# Key-RTC.net
KiCad netlist of a schematic drawn in Altium Designer
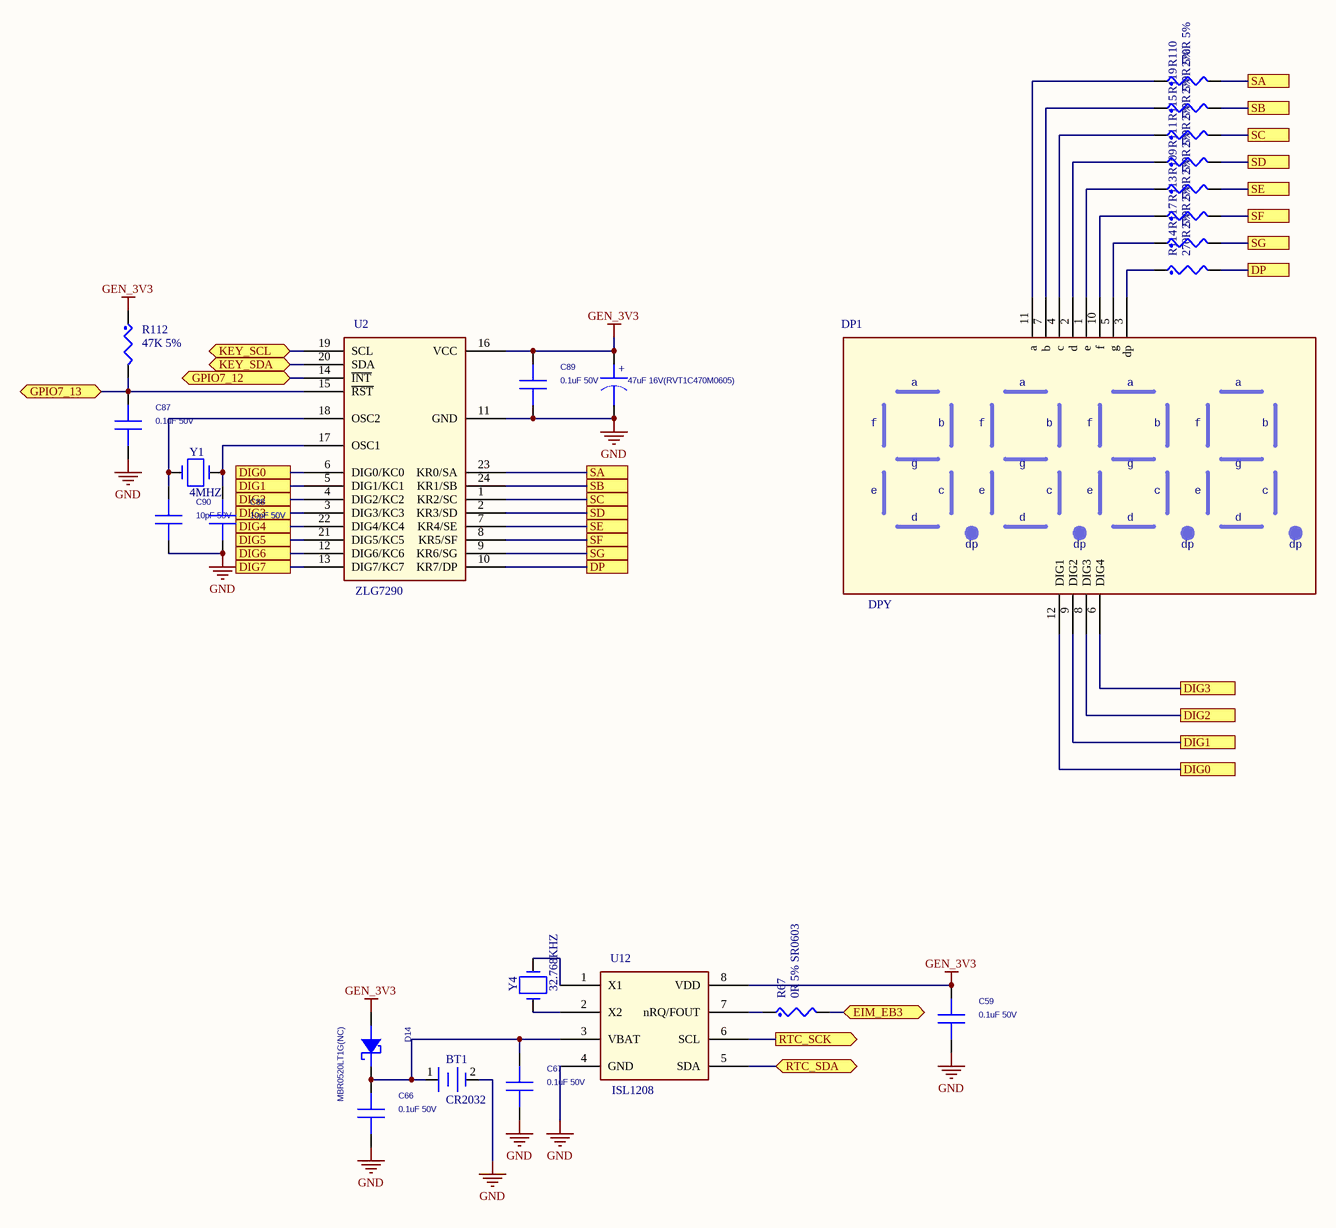
[diagram p0: Key-RTC.SchDoc]

(export (version "E")
  (design (tool "Eeschema 10.0.6"))
  (components
    (comp (ref "BT1")
      (value "CR2032")
      (footprint "CR2032")
      (libsource (lib "MY-I.MX6-SCH_Library") (part "BATTERY"))
    )
    (comp (ref "C11")
      (value "47uF 16V(RVT1C470M0605)")
      (footprint "SCA6P3X5P4")
      (description "SCA6p3x5p4")
      (fields (field (name "TOLERANCE") "20%"))
      (libsource (lib "MY-I.MX6-SCH_Library") (part "100uF-6.3V-20%-AL-LOESR-SMD_5x5"))
    )
    (comp (ref "C59")
      (value "0.1uF 50V")
      (footprint "SC0603")
      (description "Capacitor, 0.1uF, 50V, 10%, X5R, 0603")
      (fields (field (name "VOLTAGE") "6.3V") (field (name "TOLERANCE") "10%"))
      (libsource (lib "MY-I.MX6-SCH_Library") (part "0.1uF-6.3V-10%-X5R-0402"))
    )
    (comp (ref "C66")
      (value "0.1uF 50V")
      (footprint "SC0603")
      (description "Capacitor, 0.1uF, 50V, 10%, X5R, 0603")
      (fields (field (name "VOLTAGE") "6.3V") (field (name "TOLERANCE") "10%"))
      (libsource (lib "MY-I.MX6-SCH_Library") (part "0.1uF-6.3V-10%-X5R-0402"))
    )
    (comp (ref "C67")
      (value "0.1uF 50V")
      (footprint "SC0603")
      (description "Capacitor, 0.1uF, 50V, 10%, X5R, 0603")
      (fields (field (name "VOLTAGE") "6.3V") (field (name "TOLERANCE") "10%"))
      (libsource (lib "MY-I.MX6-SCH_Library") (part "0.1uF-6.3V-10%-X5R-0402"))
    )
    (comp (ref "C87")
      (value "0.1uF 50V")
      (footprint "SC0603")
      (description "Capacitor, 0.1uF, 50V, 10%, X5R, 0603")
      (fields (field (name "VOLTAGE") "6.3V") (field (name "TOLERANCE") "10%"))
      (libsource (lib "MY-I.MX6-SCH_Library") (part "0.1uF-6.3V-10%-X5R-0402"))
    )
    (comp (ref "C88")
      (value "10pF 50V")
      (footprint "SC0603")
      (description "Capacitor, 0.1uF, 50V, 10%, X5R, 0603")
      (fields (field (name "VOLTAGE") "6.3V") (field (name "TOLERANCE") "10%"))
      (libsource (lib "MY-I.MX6-SCH_Library") (part "0.1uF-6.3V-10%-X5R-0402"))
    )
    (comp (ref "C89")
      (value "0.1uF 50V")
      (footprint "SC0603")
      (description "Capacitor, 0.1uF, 50V, 10%, X5R, 0603")
      (fields (field (name "VOLTAGE") "6.3V") (field (name "TOLERANCE") "10%"))
      (libsource (lib "MY-I.MX6-SCH_Library") (part "0.1uF-6.3V-10%-X5R-0402"))
    )
    (comp (ref "C90")
      (value "10pF 50V")
      (footprint "SC0603")
      (description "Capacitor, 0.1uF, 50V, 10%, X5R, 0603")
      (fields (field (name "VOLTAGE") "6.3V") (field (name "TOLERANCE") "10%"))
      (libsource (lib "MY-I.MX6-SCH_Library") (part "0.1uF-6.3V-10%-X5R-0402"))
    )
    (comp (ref "D14")
      (value "MBR0520LT1G(NC)")
      (footprint "SOD123")
      (description "SOD123")
      (libsource (lib "MY-I.MX6-SCH_Library") (part "DIODE SCHOTTKY_Dup1"))
    )
    (comp (ref "DP1")
      (value "DPY")
      (footprint "LEDTUBE-14X30")
      (libsource (lib "MY-I.MX6-SCH_Library") (part "DPY"))
    )
    (comp (ref "R67")
      (value "0R 5% SR0603")
      (footprint "SR0603")
      (libsource (lib "MY-I.MX6-SCH_Library") (part "RES"))
    )
    (comp (ref "R109")
      (value "270R 5%")
      (footprint "SR0603")
      (description "SR0603")
      (libsource (lib "MY-I.MX6-SCH_Library") (part "RES"))
    )
    (comp (ref "R110")
      (value "270R 5%")
      (footprint "SR0603")
      (description "SR0603")
      (libsource (lib "MY-I.MX6-SCH_Library") (part "RES"))
    )
    (comp (ref "R111")
      (value "270R 5%")
      (footprint "SR0603")
      (description "SR0603")
      (libsource (lib "MY-I.MX6-SCH_Library") (part "RES"))
    )
    (comp (ref "R112")
      (value "47K 5%")
      (footprint "SR0603")
      (description "SR0603")
      (libsource (lib "MY-I.MX6-SCH_Library") (part "RES"))
    )
    (comp (ref "R113")
      (value "270R 5%")
      (footprint "SR0603")
      (description "SR0603")
      (libsource (lib "MY-I.MX6-SCH_Library") (part "RES"))
    )
    (comp (ref "R114")
      (value "270R 5%")
      (footprint "SR0603")
      (description "SR0603")
      (libsource (lib "MY-I.MX6-SCH_Library") (part "RES"))
    )
    (comp (ref "R115")
      (value "270R 5%")
      (footprint "SR0603")
      (description "SR0603")
      (libsource (lib "MY-I.MX6-SCH_Library") (part "RES"))
    )
    (comp (ref "R117")
      (value "270R 5%")
      (footprint "SR0603")
      (description "SR0603")
      (libsource (lib "MY-I.MX6-SCH_Library") (part "RES"))
    )
    (comp (ref "R119")
      (value "270R 5%")
      (footprint "SR0603")
      (description "SR0603")
      (libsource (lib "MY-I.MX6-SCH_Library") (part "RES"))
    )
    (comp (ref "U2")
      (value "ZLG7290")
      (footprint "SOP24-1P27-15X10P5")
      (description "SOP24-1p27-15x10p5")
      (libsource (lib "MY-I.MX6-SCH_Library") (part "ZLG7290"))
    )
    (comp (ref "U12")
      (value "ISL1208")
      (footprint "SOP8-1p27-5x4")
      (description "SL1208  SOP8-1p27-5x4")
      (libsource (lib "MY-I.MX6-SCH_Library") (part "ISL1208"))
    )
    (comp (ref "Y1")
      (value "4MHZ")
      (footprint "XTAL-2-5P08")
      (description "XTAL-2-5p08")
      (libsource (lib "MY-I.MX6-SCH_Library") (part "CRYSTAL_0"))
    )
    (comp (ref "Y4")
      (value "32.768KHZ")
      (footprint "SCRY2-3X1P5")
      (description "SCRY2-3x1p5")
      (libsource (lib "MY-I.MX6-SCH_Library") (part "CRYSTAL_0"))
    )
  )
  (nets
    (net (code "1") (name "/DIG0") (class "Default")
      (node (ref "DP1") (pin "12") (pinfunction "DIG1_12") (pintype "passive"))
      (node (ref "U2") (pin "6") (pinfunction "DIG0/KC0_6") (pintype "passive"))
    )
    (net (code "2") (name "/DIG1") (class "Default")
      (node (ref "DP1") (pin "9") (pinfunction "DIG2_9") (pintype "passive"))
      (node (ref "U2") (pin "5") (pinfunction "DIG1/KC1_5") (pintype "passive"))
    )
    (net (code "3") (name "/DIG2") (class "Default")
      (node (ref "DP1") (pin "8") (pinfunction "DIG3_8") (pintype "passive"))
      (node (ref "U2") (pin "4") (pinfunction "DIG2/KC2_4") (pintype "passive"))
    )
    (net (code "4") (name "/DIG3") (class "Default")
      (node (ref "DP1") (pin "6") (pinfunction "DIG4_6") (pintype "passive"))
      (node (ref "U2") (pin "3") (pinfunction "DIG3/KC3_3") (pintype "passive"))
    )
    (net (code "5") (name "/DIG4") (class "Default")
      (node (ref "U2") (pin "22") (pinfunction "DIG4/KC4_22") (pintype "passive"))
    )
    (net (code "6") (name "/DIG5") (class "Default")
      (node (ref "U2") (pin "21") (pinfunction "DIG5/KC5_21") (pintype "passive"))
    )
    (net (code "7") (name "/DIG6") (class "Default")
      (node (ref "U2") (pin "12") (pinfunction "DIG6/KC6_12") (pintype "passive"))
    )
    (net (code "8") (name "/DIG7") (class "Default")
      (node (ref "U2") (pin "13") (pinfunction "DIG7/KC7_13") (pintype "passive"))
    )
    (net (code "9") (name "/DP") (class "Default")
      (node (ref "R114") (pin "2") (pinfunction "2_2") (pintype "passive"))
      (node (ref "U2") (pin "10") (pinfunction "KR7/DP_10") (pintype "passive"))
    )
    (net (code "10") (name "/EIM_EB3") (class "Default")
      (node (ref "R67") (pin "2") (pinfunction "2_2") (pintype "passive"))
    )
    (net (code "11") (name "/GPIO7_12") (class "Default")
      (node (ref "U2") (pin "14") (pinfunction "~{INT}_14") (pintype "passive"))
    )
    (net (code "12") (name "/GPIO7_13") (class "Default")
      (node (ref "C87") (pin "1") (pinfunction "1_1") (pintype "passive"))
      (node (ref "R112") (pin "2") (pinfunction "2_2") (pintype "passive"))
      (node (ref "U2") (pin "15") (pinfunction "~{RST}_15") (pintype "passive"))
    )
    (net (code "13") (name "/KEY_SCL") (class "Default")
      (node (ref "U2") (pin "19") (pinfunction "SCL_19") (pintype "passive"))
    )
    (net (code "14") (name "/KEY_SDA") (class "Default")
      (node (ref "U2") (pin "20") (pinfunction "SDA_20") (pintype "passive"))
    )
    (net (code "15") (name "/RTC_SCK") (class "Default")
      (node (ref "U12") (pin "6") (pinfunction "SCL_6") (pintype "passive"))
    )
    (net (code "16") (name "/RTC_SDA") (class "Default")
      (node (ref "U12") (pin "5") (pinfunction "SDA_5") (pintype "passive"))
    )
    (net (code "17") (name "/SA") (class "Default")
      (node (ref "R110") (pin "2") (pinfunction "2_2") (pintype "passive"))
      (node (ref "U2") (pin "23") (pinfunction "KR0/SA_23") (pintype "passive"))
    )
    (net (code "18") (name "/SB") (class "Default")
      (node (ref "R119") (pin "2") (pinfunction "2_2") (pintype "passive"))
      (node (ref "U2") (pin "24") (pinfunction "KR1/SB_24") (pintype "passive"))
    )
    (net (code "19") (name "/SC") (class "Default")
      (node (ref "R115") (pin "2") (pinfunction "2_2") (pintype "passive"))
      (node (ref "U2") (pin "1") (pinfunction "KR2/SC_1") (pintype "passive"))
    )
    (net (code "20") (name "/SD") (class "Default")
      (node (ref "R111") (pin "2") (pinfunction "2_2") (pintype "passive"))
      (node (ref "U2") (pin "2") (pinfunction "KR3/SD_2") (pintype "passive"))
    )
    (net (code "21") (name "/SE") (class "Default")
      (node (ref "R109") (pin "2") (pinfunction "2_2") (pintype "passive"))
      (node (ref "U2") (pin "7") (pinfunction "KR4/SE_7") (pintype "passive"))
    )
    (net (code "22") (name "/SF") (class "Default")
      (node (ref "R113") (pin "2") (pinfunction "2_2") (pintype "passive"))
      (node (ref "U2") (pin "8") (pinfunction "KR5/SF_8") (pintype "passive"))
    )
    (net (code "23") (name "/SG") (class "Default")
      (node (ref "R117") (pin "2") (pinfunction "2_2") (pintype "passive"))
      (node (ref "U2") (pin "9") (pinfunction "KR6/SG_9") (pintype "passive"))
    )
    (net (code "24") (name "GEN_3V3") (class "Default")
      (node (ref "C11") (pin "1") (pinfunction "1_1") (pintype "passive"))
      (node (ref "C59") (pin "1") (pinfunction "1_1") (pintype "passive"))
      (node (ref "C89") (pin "1") (pinfunction "1_1") (pintype "passive"))
      (node (ref "D14") (pin "1") (pinfunction "ANODE_1") (pintype "passive"))
      (node (ref "R112") (pin "1") (pinfunction "1_1") (pintype "passive"))
      (node (ref "U12") (pin "8") (pinfunction "VDD_8") (pintype "passive"))
      (node (ref "U2") (pin "16") (pinfunction "VCC_16") (pintype "passive"))
    )
    (net (code "25") (name "GND") (class "Default")
      (node (ref "BT1") (pin "2") (pinfunction "2_2") (pintype "passive"))
      (node (ref "C11") (pin "2") (pinfunction "2_2") (pintype "passive"))
      (node (ref "C59") (pin "2") (pinfunction "2_2") (pintype "passive"))
      (node (ref "C66") (pin "2") (pinfunction "2_2") (pintype "passive"))
      (node (ref "C67") (pin "2") (pinfunction "2_2") (pintype "passive"))
      (node (ref "C87") (pin "2") (pinfunction "2_2") (pintype "passive"))
      (node (ref "C88") (pin "2") (pinfunction "2_2") (pintype "passive"))
      (node (ref "C89") (pin "2") (pinfunction "2_2") (pintype "passive"))
      (node (ref "C90") (pin "2") (pinfunction "2_2") (pintype "passive"))
      (node (ref "U12") (pin "4") (pinfunction "GND_4") (pintype "passive"))
      (node (ref "U2") (pin "11") (pinfunction "GND_11") (pintype "passive"))
    )
    (net (code "26") (name "Net-(D14-CATHODE)") (class "Default")
      (node (ref "BT1") (pin "1") (pinfunction "1_1") (pintype "passive"))
      (node (ref "C66") (pin "1") (pinfunction "1_1") (pintype "passive"))
      (node (ref "C67") (pin "1") (pinfunction "1_1") (pintype "passive"))
      (node (ref "D14") (pin "2") (pinfunction "CATHODE_2") (pintype "passive"))
      (node (ref "U12") (pin "3") (pinfunction "VBAT_3") (pintype "passive"))
    )
    (net (code "27") (name "Net-(DP1-a)") (class "Default")
      (node (ref "DP1") (pin "11") (pinfunction "a_11") (pintype "passive"))
      (node (ref "R110") (pin "1") (pinfunction "1_1") (pintype "passive"))
    )
    (net (code "28") (name "Net-(DP1-b)") (class "Default")
      (node (ref "DP1") (pin "7") (pinfunction "b_7") (pintype "passive"))
      (node (ref "R119") (pin "1") (pinfunction "1_1") (pintype "passive"))
    )
    (net (code "29") (name "Net-(DP1-c)") (class "Default")
      (node (ref "DP1") (pin "4") (pinfunction "c_4") (pintype "passive"))
      (node (ref "R115") (pin "1") (pinfunction "1_1") (pintype "passive"))
    )
    (net (code "30") (name "Net-(DP1-d)") (class "Default")
      (node (ref "DP1") (pin "2") (pinfunction "d_2") (pintype "passive"))
      (node (ref "R111") (pin "1") (pinfunction "1_1") (pintype "passive"))
    )
    (net (code "31") (name "Net-(DP1-dp)") (class "Default")
      (node (ref "DP1") (pin "3") (pinfunction "dp_3") (pintype "passive"))
      (node (ref "R114") (pin "1") (pinfunction "1_1") (pintype "passive"))
    )
    (net (code "32") (name "Net-(DP1-e)") (class "Default")
      (node (ref "DP1") (pin "1") (pinfunction "e_1") (pintype "passive"))
      (node (ref "R109") (pin "1") (pinfunction "1_1") (pintype "passive"))
    )
    (net (code "33") (name "Net-(DP1-f)") (class "Default")
      (node (ref "DP1") (pin "10") (pinfunction "f_10") (pintype "passive"))
      (node (ref "R113") (pin "1") (pinfunction "1_1") (pintype "passive"))
    )
    (net (code "34") (name "Net-(DP1-g)") (class "Default")
      (node (ref "DP1") (pin "5") (pinfunction "g_5") (pintype "passive"))
      (node (ref "R117") (pin "1") (pinfunction "1_1") (pintype "passive"))
    )
    (net (code "35") (name "Net-(U2-OSC1)") (class "Default")
      (node (ref "C88") (pin "1") (pinfunction "1_1") (pintype "passive"))
      (node (ref "U2") (pin "17") (pinfunction "OSC1_17") (pintype "passive"))
      (node (ref "Y1") (pin "2") (pinfunction "2_2") (pintype "passive"))
    )
    (net (code "36") (name "Net-(U2-OSC2)") (class "Default")
      (node (ref "C90") (pin "1") (pinfunction "1_1") (pintype "passive"))
      (node (ref "U2") (pin "18") (pinfunction "OSC2_18") (pintype "passive"))
      (node (ref "Y1") (pin "1") (pinfunction "1_1") (pintype "passive"))
    )
    (net (code "37") (name "Net-(U12-X1)") (class "Default")
      (node (ref "U12") (pin "1") (pinfunction "X1_1") (pintype "passive"))
      (node (ref "Y4") (pin "2") (pinfunction "2_2") (pintype "passive"))
    )
    (net (code "38") (name "Net-(U12-X2)") (class "Default")
      (node (ref "U12") (pin "2") (pinfunction "X2_2") (pintype "passive"))
      (node (ref "Y4") (pin "1") (pinfunction "1_1") (pintype "passive"))
    )
    (net (code "39") (name "Net-(U12-nRQ{slash}FOUT)") (class "Default")
      (node (ref "R67") (pin "1") (pinfunction "1_1") (pintype "passive"))
      (node (ref "U12") (pin "7") (pinfunction "nRQ/FOUT_7") (pintype "passive"))
    )
  )
)
